# MaUWB_DSTO_Pro_with_Display_v1_0.net
KiCad netlist of a schematic drawn in EAGLE
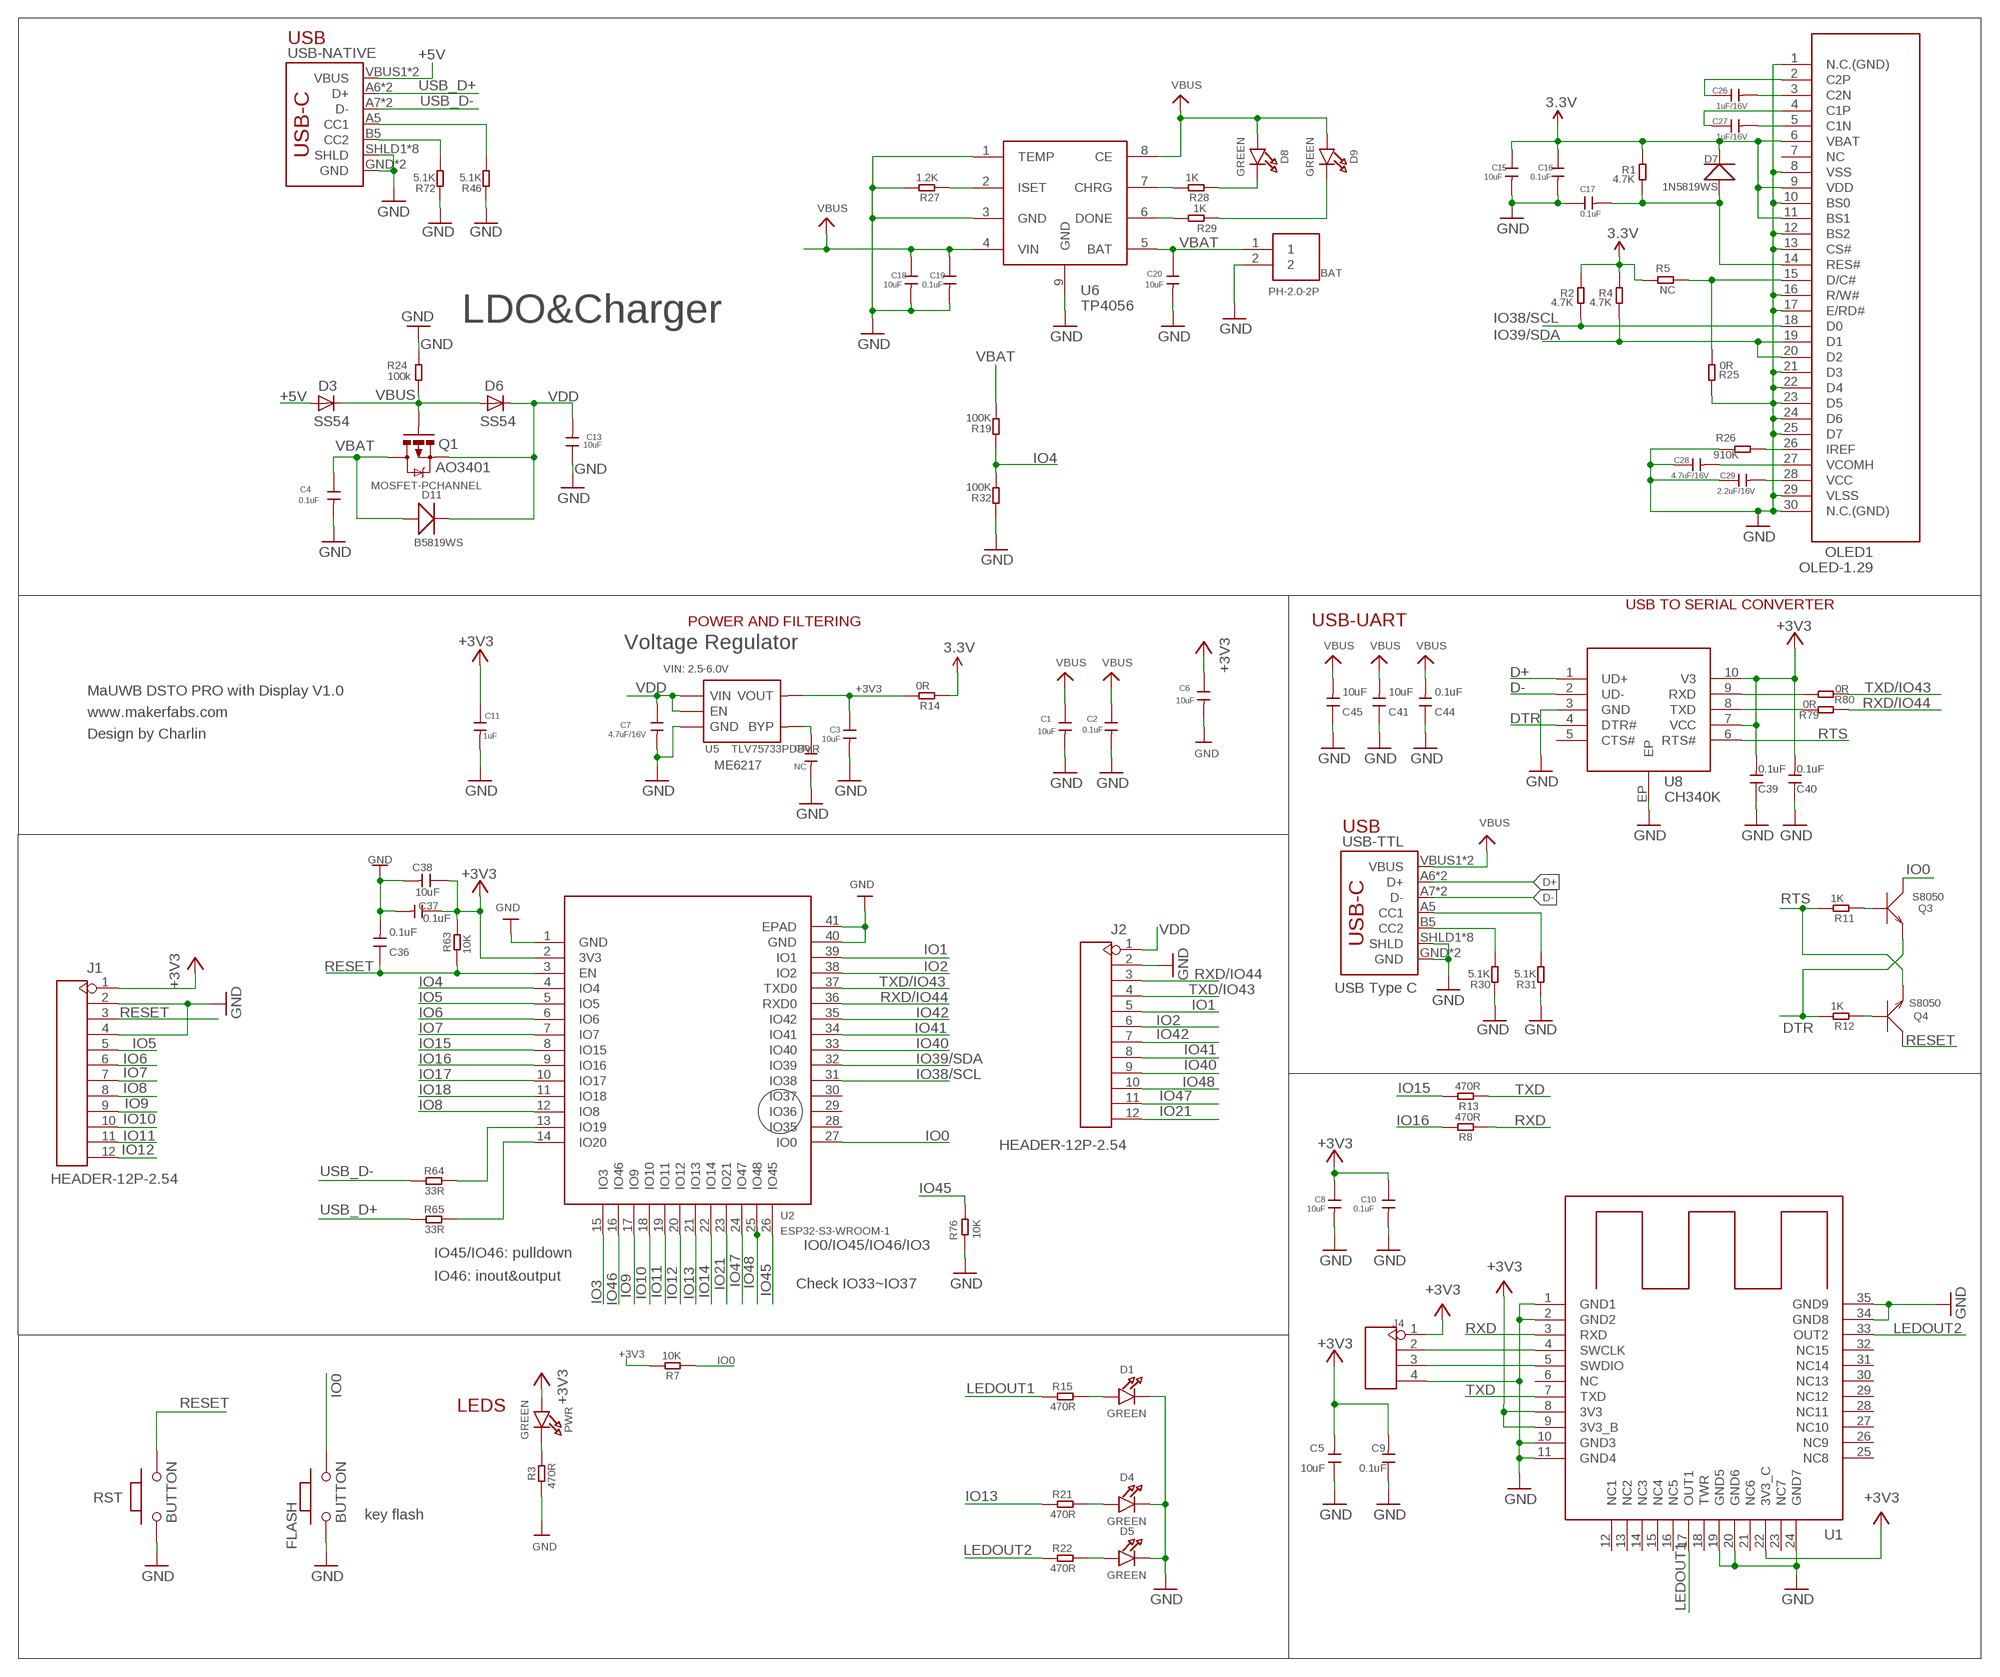
[diagram p0: schematic, sheet 1]

(export (version "E")
  (design (tool "Eeschema 10.0.6"))
  (components
    (comp (ref "BAT")
      (value "PH-2.0-2P")
      (footprint "eagle-import:PH-2.0-2P")
      (libsource (lib "eagle-import") (part "PH-2.0-2P"))
    )
    (comp (ref "C1")
      (value "10uF")
      (footprint "eagle-import:0603")
      (libsource (lib "eagle-import") (part "C-0603"))
    )
    (comp (ref "C2")
      (value "0.1uF")
      (footprint "eagle-import:0603")
      (libsource (lib "eagle-import") (part "C-0603"))
    )
    (comp (ref "C3")
      (value "10uF")
      (footprint "eagle-import:0603")
      (libsource (lib "eagle-import") (part "C-0603"))
    )
    (comp (ref "C4")
      (value "0.1uF")
      (footprint "eagle-import:0603")
      (libsource (lib "eagle-import") (part "C-0603"))
    )
    (comp (ref "C5")
      (value "10uF")
      (footprint "eagle-import:DISCRETE_C0402")
      (libsource (lib "eagle-import") (part "DISCRETE_C-0402"))
    )
    (comp (ref "C6")
      (value "10uF")
      (footprint "eagle-import:0603")
      (libsource (lib "eagle-import") (part "C-0603"))
    )
    (comp (ref "C7")
      (value "4.7uF/16V")
      (footprint "eagle-import:0603")
      (libsource (lib "eagle-import") (part "C-0603"))
    )
    (comp (ref "C8")
      (value "10uF")
      (footprint "eagle-import:0603")
      (libsource (lib "eagle-import") (part "C-0603"))
    )
    (comp (ref "C9")
      (value "0.1uF")
      (footprint "eagle-import:DISCRETE_C0402")
      (libsource (lib "eagle-import") (part "DISCRETE_C-0402"))
    )
    (comp (ref "C10")
      (value "0.1uF")
      (footprint "eagle-import:0603")
      (libsource (lib "eagle-import") (part "C-0603"))
    )
    (comp (ref "C11")
      (value "1uF")
      (footprint "eagle-import:0603")
      (libsource (lib "eagle-import") (part "C-0603"))
    )
    (comp (ref "C13")
      (value "10uF")
      (footprint "eagle-import:0603")
      (libsource (lib "eagle-import") (part "C-0603"))
    )
    (comp (ref "C15")
      (value "10uF")
      (footprint "eagle-import:0603")
      (libsource (lib "eagle-import") (part "C-0603"))
    )
    (comp (ref "C16")
      (value "0.1uF")
      (footprint "eagle-import:0603")
      (libsource (lib "eagle-import") (part "C-0603"))
    )
    (comp (ref "C17")
      (value "0.1uF")
      (footprint "eagle-import:0603")
      (libsource (lib "eagle-import") (part "C-0603"))
    )
    (comp (ref "C18")
      (value "10uF")
      (footprint "eagle-import:0603")
      (libsource (lib "eagle-import") (part "C-0603"))
    )
    (comp (ref "C19")
      (value "0.1uF")
      (footprint "eagle-import:0603")
      (libsource (lib "eagle-import") (part "C-0603"))
    )
    (comp (ref "C20")
      (value "10uF")
      (footprint "eagle-import:0603")
      (libsource (lib "eagle-import") (part "C-0603"))
    )
    (comp (ref "C26")
      (value "1uF/16V")
      (footprint "eagle-import:0603")
      (libsource (lib "eagle-import") (part "C-0603"))
    )
    (comp (ref "C27")
      (value "1uF/16V")
      (footprint "eagle-import:0603")
      (libsource (lib "eagle-import") (part "C-0603"))
    )
    (comp (ref "C28")
      (value "4.7uF/16V")
      (footprint "eagle-import:0603")
      (libsource (lib "eagle-import") (part "C-0603"))
    )
    (comp (ref "C29")
      (value "2.2uF/16V")
      (footprint "eagle-import:0603")
      (libsource (lib "eagle-import") (part "C-0603"))
    )
    (comp (ref "C30")
      (value "NC")
      (footprint "eagle-import:0603")
      (libsource (lib "eagle-import") (part "C-0603"))
    )
    (comp (ref "C36")
      (value "0.1uF")
      (footprint "eagle-import:DISCRETE_C0603")
      (libsource (lib "eagle-import") (part "DISCRETE_C-0603"))
    )
    (comp (ref "C37")
      (value "0.1uF")
      (footprint "eagle-import:DISCRETE_C0603")
      (libsource (lib "eagle-import") (part "DISCRETE_C-0603"))
    )
    (comp (ref "C38")
      (value "10uF")
      (footprint "eagle-import:DISCRETE_C0603")
      (libsource (lib "eagle-import") (part "DISCRETE_C-0603"))
    )
    (comp (ref "C39")
      (value "0.1uF")
      (footprint "eagle-import:DISCRETE_C0603")
      (libsource (lib "eagle-import") (part "DISCRETE_C-0603"))
    )
    (comp (ref "C40")
      (value "0.1uF")
      (footprint "eagle-import:DISCRETE_C0603")
      (libsource (lib "eagle-import") (part "DISCRETE_C-0603"))
    )
    (comp (ref "C41")
      (value "10uF")
      (footprint "eagle-import:DISCRETE_C0603")
      (libsource (lib "eagle-import") (part "DISCRETE_C-0603"))
    )
    (comp (ref "C44")
      (value "0.1uF")
      (footprint "eagle-import:DISCRETE_C0603")
      (libsource (lib "eagle-import") (part "DISCRETE_C-0603"))
    )
    (comp (ref "C45")
      (value "10uF")
      (footprint "eagle-import:DISCRETE_C0603")
      (libsource (lib "eagle-import") (part "DISCRETE_C-0603"))
    )
    (comp (ref "D1")
      (value "GREEN")
      (footprint "eagle-import:CHIPLED_0805_NOOUTLINE")
      (libsource (lib "eagle-import") (part "LED0805_NOOUTLINE"))
    )
    (comp (ref "D3")
      (value "SS54")
      (footprint "eagle-import:DO-214AC")
      (libsource (lib "eagle-import") (part "DIODE-DO-214AC"))
    )
    (comp (ref "D4")
      (value "GREEN")
      (footprint "eagle-import:CHIPLED_0805_NOOUTLINE")
      (libsource (lib "eagle-import") (part "LED0805_NOOUTLINE"))
    )
    (comp (ref "D5")
      (value "GREEN")
      (footprint "eagle-import:CHIPLED_0805_NOOUTLINE")
      (libsource (lib "eagle-import") (part "LED0805_NOOUTLINE"))
    )
    (comp (ref "D6")
      (value "SS54")
      (footprint "eagle-import:DO-214AC")
      (libsource (lib "eagle-import") (part "DIODE-DO-214AC"))
    )
    (comp (ref "D7")
      (value "1N5819WS")
      (footprint "eagle-import:SOD323")
      (libsource (lib "eagle-import") (part "D'0805'"))
    )
    (comp (ref "D8")
      (value "GREEN")
      (footprint "eagle-import:CHIPLED_0805_NOOUTLINE")
      (libsource (lib "eagle-import") (part "LED0805_NOOUTLINE"))
    )
    (comp (ref "D9")
      (value "GREEN")
      (footprint "eagle-import:CHIPLED_0805_NOOUTLINE")
      (libsource (lib "eagle-import") (part "LED0805_NOOUTLINE"))
    )
    (comp (ref "D11")
      (value "B5819WS")
      (footprint "eagle-import:SOD323")
      (libsource (lib "eagle-import") (part "D'0805'"))
    )
    (comp (ref "FLASH")
      (value "BUTTON")
      (footprint "eagle-import:157SW")
      (libsource (lib "eagle-import") (part "PB157"))
    )
    (comp (ref "J1")
      (value "HEADER-12P-2.54")
      (footprint "eagle-import:12P-2.54")
      (libsource (lib "eagle-import") (part "HEADER-12P-2.54"))
    )
    (comp (ref "J2")
      (value "HEADER-12P-2.54")
      (footprint "eagle-import:12P-2.54")
      (libsource (lib "eagle-import") (part "HEADER-12P-2.54"))
    )
    (comp (ref "J4")
      (value "HEADER-4P-60/35MILROUND")
      (footprint "eagle-import:4P-65_35ROUND")
      (libsource (lib "eagle-import") (part "HEADER-4P-60/35MILROUND"))
    )
    (comp (ref "OLED1")
      (value "OLED-1.29")
      (footprint "eagle-import:OLED-1.29")
      (libsource (lib "eagle-import") (part "OLED-1.29"))
    )
    (comp (ref "PWR")
      (value "GREEN")
      (footprint "eagle-import:CHIPLED_0805_NOOUTLINE")
      (libsource (lib "eagle-import") (part "LED0805_NOOUTLINE"))
    )
    (comp (ref "Q1")
      (value "MOSFET-PCHANNEL")
      (footprint "eagle-import:SOT23-3")
      (libsource (lib "eagle-import") (part "MOSFET-PCHANNEL"))
    )
    (comp (ref "Q3")
      (value "S8050")
      (footprint "eagle-import:SOT23")
      (libsource (lib "eagle-import") (part "TRANSISTOR-NPN-SOT23"))
    )
    (comp (ref "Q4")
      (value "S8050")
      (footprint "eagle-import:SOT23")
      (libsource (lib "eagle-import") (part "TRANSISTOR-NPN-SOT23"))
    )
    (comp (ref "R1")
      (value "4.7K")
      (footprint "eagle-import:R0603")
      (libsource (lib "eagle-import") (part "R-0603"))
    )
    (comp (ref "R2")
      (value "4.7K")
      (footprint "eagle-import:R0603")
      (libsource (lib "eagle-import") (part "R-0603"))
    )
    (comp (ref "R3")
      (value "470R")
      (footprint "eagle-import:R0603")
      (libsource (lib "eagle-import") (part "R-0603"))
    )
    (comp (ref "R4")
      (value "4.7K")
      (footprint "eagle-import:R0603")
      (libsource (lib "eagle-import") (part "R-0603"))
    )
    (comp (ref "R5")
      (value "NC")
      (footprint "eagle-import:R0603")
      (libsource (lib "eagle-import") (part "R-0603"))
    )
    (comp (ref "R7")
      (value "10K")
      (footprint "eagle-import:R0603")
      (libsource (lib "eagle-import") (part "R-0603"))
    )
    (comp (ref "R8")
      (value "470R")
      (footprint "eagle-import:R0603")
      (libsource (lib "eagle-import") (part "R-0603"))
    )
    (comp (ref "R11")
      (value "1K")
      (footprint "eagle-import:R0603")
      (libsource (lib "eagle-import") (part "R-0603"))
    )
    (comp (ref "R12")
      (value "1K")
      (footprint "eagle-import:R0603")
      (libsource (lib "eagle-import") (part "R-0603"))
    )
    (comp (ref "R13")
      (value "470R")
      (footprint "eagle-import:R0603")
      (libsource (lib "eagle-import") (part "R-0603"))
    )
    (comp (ref "R14")
      (value "0R")
      (footprint "eagle-import:R0603")
      (libsource (lib "eagle-import") (part "R-0603"))
    )
    (comp (ref "R15")
      (value "470R")
      (footprint "eagle-import:R0603")
      (libsource (lib "eagle-import") (part "R-0603"))
    )
    (comp (ref "R19")
      (value "100K")
      (footprint "eagle-import:DISCRETE_R0603")
      (libsource (lib "eagle-import") (part "DISCRETE_R-0603"))
    )
    (comp (ref "R21")
      (value "470R")
      (footprint "eagle-import:R0603")
      (libsource (lib "eagle-import") (part "R-0603"))
    )
    (comp (ref "R22")
      (value "470R")
      (footprint "eagle-import:R0603")
      (libsource (lib "eagle-import") (part "R-0603"))
    )
    (comp (ref "R24")
      (value "100k")
      (footprint "eagle-import:R0603")
      (libsource (lib "eagle-import") (part "R-0603"))
    )
    (comp (ref "R25")
      (value "0R")
      (footprint "eagle-import:R0603")
      (libsource (lib "eagle-import") (part "R-0603"))
    )
    (comp (ref "R26")
      (value "910K")
      (footprint "eagle-import:R0603")
      (libsource (lib "eagle-import") (part "R-0603"))
    )
    (comp (ref "R27")
      (value "1.2K")
      (footprint "eagle-import:R0603")
      (libsource (lib "eagle-import") (part "R-0603"))
    )
    (comp (ref "R28")
      (value "1K")
      (footprint "eagle-import:R0603")
      (libsource (lib "eagle-import") (part "R-0603"))
    )
    (comp (ref "R29")
      (value "1K")
      (footprint "eagle-import:R0603")
      (libsource (lib "eagle-import") (part "R-0603"))
    )
    (comp (ref "R30")
      (value "5.1K")
      (footprint "eagle-import:DISCRETE_R0603")
      (libsource (lib "eagle-import") (part "DISCRETE_R-0603"))
    )
    (comp (ref "R31")
      (value "5.1K")
      (footprint "eagle-import:DISCRETE_R0603")
      (libsource (lib "eagle-import") (part "DISCRETE_R-0603"))
    )
    (comp (ref "R32")
      (value "100K")
      (footprint "eagle-import:DISCRETE_R0603")
      (libsource (lib "eagle-import") (part "DISCRETE_R-0603"))
    )
    (comp (ref "R46")
      (value "5.1K")
      (footprint "eagle-import:DISCRETE_R0603")
      (libsource (lib "eagle-import") (part "DISCRETE_R-0603"))
    )
    (comp (ref "R63")
      (value "10K")
      (footprint "eagle-import:R0603")
      (libsource (lib "eagle-import") (part "R-0603"))
    )
    (comp (ref "R64")
      (value "33R")
      (footprint "eagle-import:R0603")
      (libsource (lib "eagle-import") (part "R-0603"))
    )
    (comp (ref "R65")
      (value "33R")
      (footprint "eagle-import:R0603")
      (libsource (lib "eagle-import") (part "R-0603"))
    )
    (comp (ref "R72")
      (value "5.1K")
      (footprint "eagle-import:DISCRETE_R0603")
      (libsource (lib "eagle-import") (part "DISCRETE_R-0603"))
    )
    (comp (ref "R76")
      (value "10K")
      (footprint "eagle-import:R0603")
      (libsource (lib "eagle-import") (part "R-0603"))
    )
    (comp (ref "R79")
      (value "0R")
      (footprint "eagle-import:R0603")
      (libsource (lib "eagle-import") (part "R-0603"))
    )
    (comp (ref "R80")
      (value "0R")
      (footprint "eagle-import:R0603")
      (libsource (lib "eagle-import") (part "R-0603"))
    )
    (comp (ref "RST")
      (value "BUTTON")
      (footprint "eagle-import:157SW")
      (libsource (lib "eagle-import") (part "PB157"))
    )
    (comp (ref "U1")
      (value "UWB-DSTO")
      (footprint "eagle-import:UWB-DSTO")
      (libsource (lib "eagle-import") (part "UWB-DSTO"))
    )
    (comp (ref "U2")
      (value "ESP32-S3-WROOM-1")
      (footprint "eagle-import:ESP32-S3-WROOM-1")
      (libsource (lib "eagle-import") (part "ESP32-S3-WROOM-1"))
    )
    (comp (ref "U5")
      (value "TLV75733PDBVR")
      (footprint "eagle-import:SOT23-5")
      (libsource (lib "eagle-import") (part "SPX3819"))
    )
    (comp (ref "U6")
      (value "TP4056")
      (footprint "eagle-import:SOP8-1.27P")
      (libsource (lib "eagle-import") (part "TP4056"))
    )
    (comp (ref "U8")
      (value "CH340K")
      (footprint "eagle-import:ESOP-10-EP-150MIL")
      (libsource (lib "eagle-import") (part "CH340K"))
    )
    (comp (ref "USB-NATIVE")
      (value "USB_C5")
      (footprint "eagle-import:USB-C-16P-5")
      (libsource (lib "eagle-import") (part "USB_C5"))
    )
    (comp (ref "USB-TTL")
      (value "USB_C5")
      (footprint "eagle-import:USB-C-16P-5")
      (libsource (lib "eagle-import") (part "USB_C5"))
    )
  )
  (nets
    (net (code "1") (name "+3V3") (class "Default")
      (node (ref "C10") (pin "1") (pinfunction "1_1") (pintype "passive"))
      (node (ref "C11") (pin "1") (pinfunction "1_1") (pintype "passive"))
      (node (ref "C3") (pin "1") (pinfunction "1_1") (pintype "passive"))
      (node (ref "C37") (pin "1") (pinfunction "1_1") (pintype "passive"))
      (node (ref "C38") (pin "1") (pinfunction "1_1") (pintype "passive"))
      (node (ref "C39") (pin "2") (pinfunction "2_2") (pintype "passive"))
      (node (ref "C40") (pin "2") (pinfunction "2_2") (pintype "passive"))
      (node (ref "C5") (pin "2") (pinfunction "2_2") (pintype "passive"))
      (node (ref "C6") (pin "1") (pinfunction "1_1") (pintype "passive"))
      (node (ref "C8") (pin "1") (pinfunction "1_1") (pintype "passive"))
      (node (ref "C9") (pin "2") (pinfunction "2_2") (pintype "passive"))
      (node (ref "J1") (pin "1") (pinfunction "1_1") (pintype "bidirectional"))
      (node (ref "J4") (pin "1") (pinfunction "P$1_1") (pintype "bidirectional"))
      (node (ref "PWR") (pin "A") (pinfunction "A_A") (pintype "passive"))
      (node (ref "R14") (pin "2") (pinfunction "2_2") (pintype "passive"))
      (node (ref "R63") (pin "2") (pinfunction "2_2") (pintype "passive"))
      (node (ref "R7") (pin "2") (pinfunction "2_2") (pintype "passive"))
      (node (ref "U1") (pin "22") (pinfunction "3V3_C_22") (pintype "bidirectional"))
      (node (ref "U1") (pin "8") (pinfunction "3V3_8") (pintype "bidirectional"))
      (node (ref "U1") (pin "9") (pinfunction "3V3_B_9") (pintype "bidirectional"))
      (node (ref "U2") (pin "2") (pinfunction "3V3_2") (pintype "bidirectional"))
      (node (ref "U5") (pin "5") (pinfunction "VOUT_5") (pintype "bidirectional"))
      (node (ref "U8") (pin "10") (pinfunction "V3_10") (pintype "bidirectional"))
      (node (ref "U8") (pin "7") (pinfunction "VCC_7") (pintype "bidirectional"))
    )
    (net (code "2") (name "/+5V") (class "Default")
      (node (ref "D3") (pin "A") (pinfunction "A_A") (pintype "passive"))
      (node (ref "USB-NATIVE") (pin "VBUS1") (pinfunction "VBUS_VBUS1") (pintype "bidirectional"))
      (node (ref "USB-NATIVE") (pin "VBUS2") (pinfunction "VBUS_VBUS2") (pintype "bidirectional"))
    )
    (net (code "3") (name "/DTR") (class "Default")
      (node (ref "Q3") (pin "2") (pinfunction "E_2") (pintype "passive"))
      (node (ref "R12") (pin "2") (pinfunction "2_2") (pintype "passive"))
      (node (ref "U8") (pin "4") (pinfunction "DTR#_4") (pintype "bidirectional"))
    )
    (net (code "4") (name "/IO0") (class "Default")
      (node (ref "FLASH") (pin "2") (pinfunction "2_2") (pintype "passive"))
      (node (ref "Q3") (pin "3") (pinfunction "C_3") (pintype "passive"))
      (node (ref "R7") (pin "1") (pinfunction "1_1") (pintype "passive"))
      (node (ref "U2") (pin "27") (pinfunction "IO0_27") (pintype "bidirectional"))
    )
    (net (code "5") (name "/IO1") (class "Default")
      (node (ref "J2") (pin "5") (pinfunction "5_5") (pintype "bidirectional"))
      (node (ref "U2") (pin "39") (pinfunction "IO1_39") (pintype "bidirectional"))
    )
    (net (code "6") (name "/IO2") (class "Default")
      (node (ref "J2") (pin "6") (pinfunction "6_6") (pintype "bidirectional"))
      (node (ref "U2") (pin "38") (pinfunction "IO2_38") (pintype "bidirectional"))
    )
    (net (code "7") (name "/IO3") (class "Default")
      (node (ref "U2") (pin "15") (pinfunction "IO3_15") (pintype "bidirectional"))
    )
    (net (code "8") (name "/IO4") (class "Default")
      (node (ref "R19") (pin "1") (pinfunction "1_1") (pintype "passive"))
      (node (ref "R32") (pin "2") (pinfunction "2_2") (pintype "passive"))
      (node (ref "U2") (pin "4") (pinfunction "IO4_4") (pintype "bidirectional"))
    )
    (net (code "9") (name "/IO5") (class "Default")
      (node (ref "J1") (pin "5") (pinfunction "5_5") (pintype "bidirectional"))
      (node (ref "U2") (pin "5") (pinfunction "IO5_5") (pintype "bidirectional"))
    )
    (net (code "10") (name "/IO6") (class "Default")
      (node (ref "J1") (pin "6") (pinfunction "6_6") (pintype "bidirectional"))
      (node (ref "U2") (pin "6") (pinfunction "IO6_6") (pintype "bidirectional"))
    )
    (net (code "11") (name "/IO7") (class "Default")
      (node (ref "J1") (pin "7") (pinfunction "7_7") (pintype "bidirectional"))
      (node (ref "U2") (pin "7") (pinfunction "IO7_7") (pintype "bidirectional"))
    )
    (net (code "12") (name "/IO8") (class "Default")
      (node (ref "J1") (pin "8") (pinfunction "8_8") (pintype "bidirectional"))
      (node (ref "U2") (pin "12") (pinfunction "IO8_12") (pintype "bidirectional"))
    )
    (net (code "13") (name "/IO9") (class "Default")
      (node (ref "J1") (pin "9") (pinfunction "9_9") (pintype "bidirectional"))
      (node (ref "U2") (pin "17") (pinfunction "IO9_17") (pintype "bidirectional"))
    )
    (net (code "14") (name "/IO10") (class "Default")
      (node (ref "J1") (pin "10") (pinfunction "10_10") (pintype "bidirectional"))
      (node (ref "U2") (pin "18") (pinfunction "IO10_18") (pintype "bidirectional"))
    )
    (net (code "15") (name "/IO11") (class "Default")
      (node (ref "J1") (pin "11") (pinfunction "11_11") (pintype "bidirectional"))
      (node (ref "U2") (pin "19") (pinfunction "IO11_19") (pintype "bidirectional"))
    )
    (net (code "16") (name "/IO12") (class "Default")
      (node (ref "J1") (pin "12") (pinfunction "12_12") (pintype "bidirectional"))
      (node (ref "U2") (pin "20") (pinfunction "IO12_20") (pintype "bidirectional"))
    )
    (net (code "17") (name "/IO13") (class "Default")
      (node (ref "R21") (pin "1") (pinfunction "1_1") (pintype "passive"))
      (node (ref "U2") (pin "21") (pinfunction "IO13_21") (pintype "bidirectional"))
    )
    (net (code "18") (name "/IO14") (class "Default")
      (node (ref "U2") (pin "22") (pinfunction "IO14_22") (pintype "bidirectional"))
    )
    (net (code "19") (name "/IO15") (class "Default")
      (node (ref "R13") (pin "2") (pinfunction "2_2") (pintype "passive"))
      (node (ref "U2") (pin "8") (pinfunction "IO15_8") (pintype "bidirectional"))
    )
    (net (code "20") (name "/IO16") (class "Default")
      (node (ref "R8") (pin "2") (pinfunction "2_2") (pintype "passive"))
      (node (ref "U2") (pin "9") (pinfunction "IO16_9") (pintype "bidirectional"))
    )
    (net (code "21") (name "/IO17") (class "Default")
      (node (ref "U2") (pin "10") (pinfunction "IO17_10") (pintype "bidirectional"))
    )
    (net (code "22") (name "/IO18") (class "Default")
      (node (ref "U2") (pin "11") (pinfunction "IO18_11") (pintype "bidirectional"))
    )
    (net (code "23") (name "/IO21") (class "Default")
      (node (ref "J2") (pin "12") (pinfunction "12_12") (pintype "bidirectional"))
      (node (ref "U2") (pin "23") (pinfunction "IO21_23") (pintype "bidirectional"))
    )
    (net (code "24") (name "/IO38{slash}SCL") (class "Default")
      (node (ref "OLED1") (pin "18") (pinfunction "D0_18") (pintype "bidirectional"))
      (node (ref "R2") (pin "1") (pinfunction "1_1") (pintype "passive"))
      (node (ref "U2") (pin "31") (pinfunction "IO38_31") (pintype "bidirectional"))
    )
    (net (code "25") (name "/IO39{slash}SDA") (class "Default")
      (node (ref "OLED1") (pin "19") (pinfunction "D1_19") (pintype "bidirectional"))
      (node (ref "OLED1") (pin "20") (pinfunction "D2_20") (pintype "bidirectional"))
      (node (ref "R4") (pin "1") (pinfunction "1_1") (pintype "passive"))
      (node (ref "U2") (pin "32") (pinfunction "IO39_32") (pintype "bidirectional"))
    )
    (net (code "26") (name "/IO40") (class "Default")
      (node (ref "J2") (pin "9") (pinfunction "9_9") (pintype "bidirectional"))
      (node (ref "U2") (pin "33") (pinfunction "IO40_33") (pintype "bidirectional"))
    )
    (net (code "27") (name "/IO41") (class "Default")
      (node (ref "J2") (pin "8") (pinfunction "8_8") (pintype "bidirectional"))
      (node (ref "U2") (pin "34") (pinfunction "IO41_34") (pintype "bidirectional"))
    )
    (net (code "28") (name "/IO42") (class "Default")
      (node (ref "J2") (pin "7") (pinfunction "7_7") (pintype "bidirectional"))
      (node (ref "U2") (pin "35") (pinfunction "IO42_35") (pintype "bidirectional"))
    )
    (net (code "29") (name "/IO45") (class "Default")
      (node (ref "R76") (pin "2") (pinfunction "2_2") (pintype "passive"))
      (node (ref "U2") (pin "26") (pinfunction "IO45_26") (pintype "bidirectional"))
    )
    (net (code "30") (name "/IO46") (class "Default")
      (node (ref "U2") (pin "16") (pinfunction "IO46_16") (pintype "bidirectional"))
    )
    (net (code "31") (name "/IO47") (class "Default")
      (node (ref "J2") (pin "11") (pinfunction "11_11") (pintype "bidirectional"))
      (node (ref "U2") (pin "24") (pinfunction "IO47_24") (pintype "bidirectional"))
    )
    (net (code "32") (name "/IO48") (class "Default")
      (node (ref "J2") (pin "10") (pinfunction "10_10") (pintype "bidirectional"))
      (node (ref "U2") (pin "25") (pinfunction "IO48_25") (pintype "bidirectional"))
    )
    (net (code "33") (name "/LEDOUT1") (class "Default")
      (node (ref "R15") (pin "1") (pinfunction "1_1") (pintype "passive"))
      (node (ref "U1") (pin "17") (pinfunction "OUT1_17") (pintype "bidirectional"))
    )
    (net (code "34") (name "/LEDOUT2") (class "Default")
      (node (ref "R22") (pin "1") (pinfunction "1_1") (pintype "passive"))
      (node (ref "U1") (pin "33") (pinfunction "OUT2_33") (pintype "bidirectional"))
    )
    (net (code "35") (name "/RESET") (class "Default")
      (node (ref "C36") (pin "1") (pinfunction "1_1") (pintype "passive"))
      (node (ref "J1") (pin "3") (pinfunction "3_3") (pintype "bidirectional"))
      (node (ref "Q4") (pin "3") (pinfunction "C_3") (pintype "passive"))
      (node (ref "R63") (pin "1") (pinfunction "1_1") (pintype "passive"))
      (node (ref "RST") (pin "2") (pinfunction "2_2") (pintype "passive"))
      (node (ref "U2") (pin "3") (pinfunction "EN_3") (pintype "bidirectional"))
    )
    (net (code "36") (name "/RTS") (class "Default")
      (node (ref "Q4") (pin "2") (pinfunction "E_2") (pintype "passive"))
      (node (ref "R11") (pin "2") (pinfunction "2_2") (pintype "passive"))
      (node (ref "U8") (pin "6") (pinfunction "RTS#_6") (pintype "bidirectional"))
    )
    (net (code "37") (name "/RXD") (class "Default")
      (node (ref "R8") (pin "1") (pinfunction "1_1") (pintype "passive"))
      (node (ref "U1") (pin "3") (pinfunction "RXD_3") (pintype "bidirectional"))
    )
    (net (code "38") (name "/RXD{slash}IO44") (class "Default")
      (node (ref "J2") (pin "3") (pinfunction "3_3") (pintype "bidirectional"))
      (node (ref "R79") (pin "1") (pinfunction "1_1") (pintype "passive"))
      (node (ref "U2") (pin "36") (pinfunction "RXD0_36") (pintype "bidirectional"))
    )
    (net (code "39") (name "/TXD") (class "Default")
      (node (ref "R13") (pin "1") (pinfunction "1_1") (pintype "passive"))
      (node (ref "U1") (pin "7") (pinfunction "TXD_7") (pintype "bidirectional"))
    )
    (net (code "40") (name "/TXD{slash}IO43") (class "Default")
      (node (ref "J2") (pin "4") (pinfunction "4_4") (pintype "bidirectional"))
      (node (ref "R80") (pin "1") (pinfunction "1_1") (pintype "passive"))
      (node (ref "U2") (pin "37") (pinfunction "TXD0_37") (pintype "bidirectional"))
    )
    (net (code "41") (name "/USB_D+") (class "Default")
      (node (ref "R65") (pin "1") (pinfunction "1_1") (pintype "passive"))
      (node (ref "USB-NATIVE") (pin "A6") (pinfunction "D+_A6") (pintype "bidirectional"))
      (node (ref "USB-NATIVE") (pin "B6") (pinfunction "D+_B6") (pintype "bidirectional"))
    )
    (net (code "42") (name "/USB_D-") (class "Default")
      (node (ref "R64") (pin "1") (pinfunction "1_1") (pintype "passive"))
      (node (ref "USB-NATIVE") (pin "A7") (pinfunction "D-_A7") (pintype "bidirectional"))
      (node (ref "USB-NATIVE") (pin "B7") (pinfunction "D-_B7") (pintype "bidirectional"))
    )
    (net (code "43") (name "/VBAT") (class "Default")
      (node (ref "BAT") (pin "1") (pinfunction "1_1") (pintype "bidirectional"))
      (node (ref "C20") (pin "1") (pinfunction "1_1") (pintype "passive"))
      (node (ref "C4") (pin "1") (pinfunction "1_1") (pintype "passive"))
      (node (ref "D11") (pin "+") (pinfunction "+_+") (pintype "passive"))
      (node (ref "Q1") (pin "3") (pinfunction "D_3") (pintype "passive"))
      (node (ref "R19") (pin "2") (pinfunction "2_2") (pintype "passive"))
      (node (ref "U6") (pin "5") (pinfunction "BAT_5") (pintype "bidirectional"))
    )
    (net (code "44") (name "/VDD") (class "Default")
      (node (ref "C13") (pin "2") (pinfunction "2_2") (pintype "passive"))
      (node (ref "C7") (pin "1") (pinfunction "1_1") (pintype "passive"))
      (node (ref "D11") (pin "-") (pinfunction "-_-") (pintype "passive"))
      (node (ref "D6") (pin "C") (pinfunction "C_C") (pintype "passive"))
      (node (ref "J2") (pin "1") (pinfunction "1_1") (pintype "bidirectional"))
      (node (ref "Q1") (pin "2") (pinfunction "S_2") (pintype "passive"))
      (node (ref "U5") (pin "1") (pinfunction "VIN_1") (pintype "bidirectional"))
      (node (ref "U5") (pin "3") (pinfunction "EN_3") (pintype "bidirectional"))
    )
    (net (code "45") (name "3.3V") (class "Default")
      (node (ref "C15") (pin "1") (pinfunction "1_1") (pintype "passive"))
      (node (ref "C16") (pin "1") (pinfunction "1_1") (pintype "passive"))
      (node (ref "D7") (pin "-") (pinfunction "-_-") (pintype "passive"))
      (node (ref "OLED1") (pin "11") (pinfunction "BS1_11") (pintype "bidirectional"))
      (node (ref "OLED1") (pin "6") (pinfunction "VBAT_6") (pintype "bidirectional"))
      (node (ref "OLED1") (pin "9") (pinfunction "VDD_9") (pintype "bidirectional"))
      (node (ref "R1") (pin "2") (pinfunction "2_2") (pintype "passive"))
      (node (ref "R14") (pin "1") (pinfunction "1_1") (pintype "passive"))
      (node (ref "R2") (pin "2") (pinfunction "2_2") (pintype "passive"))
      (node (ref "R4") (pin "2") (pinfunction "2_2") (pintype "passive"))
      (node (ref "R5") (pin "2") (pinfunction "2_2") (pintype "passive"))
    )
    (net (code "46") (name "D+") (class "Default")
      (node (ref "U8") (pin "1") (pinfunction "UD+_1") (pintype "bidirectional"))
      (node (ref "USB-TTL") (pin "A6") (pinfunction "D+_A6") (pintype "bidirectional"))
      (node (ref "USB-TTL") (pin "B6") (pinfunction "D+_B6") (pintype "bidirectional"))
    )
    (net (code "47") (name "D-") (class "Default")
      (node (ref "U8") (pin "2") (pinfunction "UD-_2") (pintype "bidirectional"))
      (node (ref "USB-TTL") (pin "A7") (pinfunction "D-_A7") (pintype "bidirectional"))
      (node (ref "USB-TTL") (pin "B7") (pinfunction "D-_B7") (pintype "bidirectional"))
    )
    (net (code "48") (name "GND") (class "Default")
      (node (ref "BAT") (pin "2") (pinfunction "2_2") (pintype "bidirectional"))
      (node (ref "C1") (pin "2") (pinfunction "2_2") (pintype "passive"))
      (node (ref "C10") (pin "2") (pinfunction "2_2") (pintype "passive"))
      (node (ref "C11") (pin "2") (pinfunction "2_2") (pintype "passive"))
      (node (ref "C13") (pin "1") (pinfunction "1_1") (pintype "passive"))
      (node (ref "C15") (pin "2") (pinfunction "2_2") (pintype "passive"))
      (node (ref "C16") (pin "2") (pinfunction "2_2") (pintype "passive"))
      (node (ref "C17") (pin "1") (pinfunction "1_1") (pintype "passive"))
      (node (ref "C18") (pin "2") (pinfunction "2_2") (pintype "passive"))
      (node (ref "C19") (pin "2") (pinfunction "2_2") (pintype "passive"))
      (node (ref "C2") (pin "2") (pinfunction "2_2") (pintype "passive"))
      (node (ref "C20") (pin "2") (pinfunction "2_2") (pintype "passive"))
      (node (ref "C28") (pin "1") (pinfunction "1_1") (pintype "passive"))
      (node (ref "C29") (pin "1") (pinfunction "1_1") (pintype "passive"))
      (node (ref "C3") (pin "2") (pinfunction "2_2") (pintype "passive"))
      (node (ref "C30") (pin "2") (pinfunction "2_2") (pintype "passive"))
      (node (ref "C36") (pin "2") (pinfunction "2_2") (pintype "passive"))
      (node (ref "C37") (pin "2") (pinfunction "2_2") (pintype "passive"))
      (node (ref "C38") (pin "2") (pinfunction "2_2") (pintype "passive"))
      (node (ref "C39") (pin "1") (pinfunction "1_1") (pintype "passive"))
      (node (ref "C4") (pin "2") (pinfunction "2_2") (pintype "passive"))
      (node (ref "C40") (pin "1") (pinfunction "1_1") (pintype "passive"))
      (node (ref "C41") (pin "1") (pinfunction "1_1") (pintype "passive"))
      (node (ref "C44") (pin "1") (pinfunction "1_1") (pintype "passive"))
      (node (ref "C45") (pin "1") (pinfunction "1_1") (pintype "passive"))
      (node (ref "C5") (pin "1") (pinfunction "1_1") (pintype "passive"))
      (node (ref "C6") (pin "2") (pinfunction "2_2") (pintype "passive"))
      (node (ref "C7") (pin "2") (pinfunction "2_2") (pintype "passive"))
      (node (ref "C8") (pin "2") (pinfunction "2_2") (pintype "passive"))
      (node (ref "C9") (pin "1") (pinfunction "1_1") (pintype "passive"))
      (node (ref "D1") (pin "C") (pinfunction "C_C") (pintype "passive"))
      (node (ref "D4") (pin "C") (pinfunction "C_C") (pintype "passive"))
      (node (ref "D5") (pin "C") (pinfunction "C_C") (pintype "passive"))
      (node (ref "FLASH") (pin "1") (pinfunction "1_1") (pintype "passive"))
      (node (ref "J1") (pin "2") (pinfunction "2_2") (pintype "bidirectional"))
      (node (ref "J1") (pin "4") (pinfunction "4_4") (pintype "bidirectional"))
      (node (ref "J2") (pin "2") (pinfunction "2_2") (pintype "bidirectional"))
      (node (ref "J4") (pin "4") (pinfunction "P$4_4") (pintype "bidirectional"))
      (node (ref "OLED1") (pin "1") (pinfunction "N.C.(GND)_1") (pintype "bidirectional"))
      (node (ref "OLED1") (pin "10") (pinfunction "BS0_10") (pintype "bidirectional"))
      (node (ref "OLED1") (pin "12") (pinfunction "BS2_12") (pintype "bidirectional"))
      (node (ref "OLED1") (pin "13") (pinfunction "CS#_13") (pintype "bidirectional"))
      (node (ref "OLED1") (pin "16") (pinfunction "R/W#_16") (pintype "bidirectional"))
      (node (ref "OLED1") (pin "17") (pinfunction "E/RD#_17") (pintype "bidirectional"))
      (node (ref "OLED1") (pin "21") (pinfunction "D3_21") (pintype "bidirectional"))
      (node (ref "OLED1") (pin "22") (pinfunction "D4_22") (pintype "bidirectional"))
      (node (ref "OLED1") (pin "23") (pinfunction "D5_23") (pintype "bidirectional"))
      (node (ref "OLED1") (pin "24") (pinfunction "D6_24") (pintype "bidirectional"))
      (node (ref "OLED1") (pin "25") (pinfunction "D7_25") (pintype "bidirectional"))
      (node (ref "OLED1") (pin "29") (pinfunction "VLSS_29") (pintype "bidirectional"))
      (node (ref "OLED1") (pin "30") (pinfunction "N.C.(GND)_30") (pintype "bidirectional"))
      (node (ref "OLED1") (pin "8") (pinfunction "VSS_8") (pintype "bidirectional"))
      (node (ref "R24") (pin "2") (pinfunction "2_2") (pintype "passive"))
      (node (ref "R25") (pin "2") (pinfunction "2_2") (pintype "passive"))
      (node (ref "R26") (pin "2") (pinfunction "2_2") (pintype "passive"))
      (node (ref "R27") (pin "2") (pinfunction "2_2") (pintype "passive"))
      (node (ref "R3") (pin "1") (pinfunction "1_1") (pintype "passive"))
      (node (ref "R30") (pin "1") (pinfunction "1_1") (pintype "passive"))
      (node (ref "R31") (pin "1") (pinfunction "1_1") (pintype "passive"))
      (node (ref "R32") (pin "1") (pinfunction "1_1") (pintype "passive"))
      (node (ref "R46") (pin "1") (pinfunction "1_1") (pintype "passive"))
      (node (ref "R72") (pin "1") (pinfunction "1_1") (pintype "passive"))
      (node (ref "R76") (pin "1") (pinfunction "1_1") (pintype "passive"))
      (node (ref "RST") (pin "1") (pinfunction "1_1") (pintype "passive"))
      (node (ref "U1") (pin "1") (pinfunction "GND1_1") (pintype "bidirectional"))
      (node (ref "U1") (pin "10") (pinfunction "GND3_10") (pintype "bidirectional"))
      (node (ref "U1") (pin "11") (pinfunction "GND4_11") (pintype "bidirectional"))
      (node (ref "U1") (pin "19") (pinfunction "GND5_19") (pintype "bidirectional"))
      (node (ref "U1") (pin "2") (pinfunction "GND2_2") (pintype "bidirectional"))
      (node (ref "U1") (pin "20") (pinfunction "GND6_20") (pintype "bidirectional"))
      (node (ref "U1") (pin "24") (pinfunction "GND7_24") (pintype "bidirectional"))
      (node (ref "U1") (pin "34") (pinfunction "GND8_34") (pintype "bidirectional"))
      (node (ref "U1") (pin "35") (pinfunction "GND9_35") (pintype "bidirectional"))
      (node (ref "U2") (pin "1") (pinfunction "GND_1") (pintype "bidirectional"))
      (node (ref "U2") (pin "40") (pinfunction "GND_40") (pintype "bidirectional"))
      (node (ref "U2") (pin "41") (pinfunction "EPAD_41") (pintype "bidirectional"))
      (node (ref "U5") (pin "2") (pinfunction "GND_2") (pintype "bidirectional"))
      (node (ref "U6") (pin "1") (pinfunction "TEMP_1") (pintype "bidirectional"))
      (node (ref "U6") (pin "3") (pinfunction "GND_3") (pintype "bidirectional"))
      (node (ref "U6") (pin "9") (pinfunction "GND_9") (pintype "bidirectional"))
      (node (ref "U8") (pin "3") (pinfunction "GND_3") (pintype "bidirectional"))
      (node (ref "U8") (pin "EP") (pinfunction "EP_EP") (pintype "bidirectional"))
      (node (ref "USB-NATIVE") (pin "GND") (pinfunction "GND_GND") (pintype "bidirectional"))
      (node (ref "USB-NATIVE") (pin "GND2") (pinfunction "GND_GND2") (pintype "bidirectional"))
      (node (ref "USB-NATIVE") (pin "SHLD1") (pinfunction "SHLD_SHLD1") (pintype "bidirectional"))
      (node (ref "USB-NATIVE") (pin "SHLD2") (pinfunction "SHLD_SHLD2") (pintype "bidirectional"))
      (node (ref "USB-NATIVE") (pin "SHLD3") (pinfunction "SHLD_SHLD3") (pintype "bidirectional"))
      (node (ref "USB-NATIVE") (pin "SHLD4") (pinfunction "SHLD_SHLD4") (pintype "bidirectional"))
      (node (ref "USB-NATIVE") (pin "SHLD5") (pinfunction "SHLD_SHLD5") (pintype "bidirectional"))
      (node (ref "USB-NATIVE") (pin "SHLD6") (pinfunction "SHLD_SHLD6") (pintype "bidirectional"))
      (node (ref "USB-NATIVE") (pin "SHLD7") (pinfunction "SHLD_SHLD7") (pintype "bidirectional"))
      (node (ref "USB-NATIVE") (pin "SHLD8") (pinfunction "SHLD_SHLD8") (pintype "bidirectional"))
      (node (ref "USB-TTL") (pin "GND") (pinfunction "GND_GND") (pintype "bidirectional"))
      (node (ref "USB-TTL") (pin "GND2") (pinfunction "GND_GND2") (pintype "bidirectional"))
      (node (ref "USB-TTL") (pin "SHLD1") (pinfunction "SHLD_SHLD1") (pintype "bidirectional"))
      (node (ref "USB-TTL") (pin "SHLD2") (pinfunction "SHLD_SHLD2") (pintype "bidirectional"))
      (node (ref "USB-TTL") (pin "SHLD3") (pinfunction "SHLD_SHLD3") (pintype "bidirectional"))
      (node (ref "USB-TTL") (pin "SHLD4") (pinfunction "SHLD_SHLD4") (pintype "bidirectional"))
      (node (ref "USB-TTL") (pin "SHLD5") (pinfunction "SHLD_SHLD5") (pintype "bidirectional"))
      (node (ref "USB-TTL") (pin "SHLD6") (pinfunction "SHLD_SHLD6") (pintype "bidirectional"))
      (node (ref "USB-TTL") (pin "SHLD7") (pinfunction "SHLD_SHLD7") (pintype "bidirectional"))
      (node (ref "USB-TTL") (pin "SHLD8") (pinfunction "SHLD_SHLD8") (pintype "bidirectional"))
    )
    (net (code "49") (name "Net-(D1-PadA)") (class "Default")
      (node (ref "D1") (pin "A") (pinfunction "A_A") (pintype "passive"))
      (node (ref "R15") (pin "2") (pinfunction "2_2") (pintype "passive"))
    )
    (net (code "50") (name "Net-(D4-PadA)") (class "Default")
      (node (ref "D4") (pin "A") (pinfunction "A_A") (pintype "passive"))
      (node (ref "R21") (pin "2") (pinfunction "2_2") (pintype "passive"))
    )
    (net (code "51") (name "Net-(D5-PadA)") (class "Default")
      (node (ref "D5") (pin "A") (pinfunction "A_A") (pintype "passive"))
      (node (ref "R22") (pin "2") (pinfunction "2_2") (pintype "passive"))
    )
    (net (code "52") (name "Net-(D8-PadC)") (class "Default")
      (node (ref "D8") (pin "C") (pinfunction "C_C") (pintype "passive"))
      (node (ref "R28") (pin "1") (pinfunction "1_1") (pintype "passive"))
    )
    (net (code "53") (name "Net-(D9-PadC)") (class "Default")
      (node (ref "D9") (pin "C") (pinfunction "C_C") (pintype "passive"))
      (node (ref "R29") (pin "1") (pinfunction "1_1") (pintype "passive"))
    )
    (net (code "54") (name "Net-(J4-P$2)") (class "Default")
      (node (ref "J4") (pin "2") (pinfunction "P$2_2") (pintype "bidirectional"))
      (node (ref "U1") (pin "4") (pinfunction "SWCLK_4") (pintype "bidirectional"))
    )
    (net (code "55") (name "Net-(J4-P$3)") (class "Default")
      (node (ref "J4") (pin "3") (pinfunction "P$3_3") (pintype "bidirectional"))
      (node (ref "U1") (pin "5") (pinfunction "SWDIO_5") (pintype "bidirectional"))
    )
    (net (code "56") (name "Net-(OLED1-C1N)") (class "Default")
      (node (ref "C27") (pin "2") (pinfunction "2_2") (pintype "passive"))
      (node (ref "OLED1") (pin "5") (pinfunction "C1N_5") (pintype "bidirectional"))
    )
    (net (code "57") (name "Net-(OLED1-C1P)") (class "Default")
      (node (ref "C27") (pin "1") (pinfunction "1_1") (pintype "passive"))
      (node (ref "OLED1") (pin "4") (pinfunction "C1P_4") (pintype "bidirectional"))
    )
    (net (code "58") (name "Net-(OLED1-C2N)") (class "Default")
      (node (ref "C26") (pin "2") (pinfunction "2_2") (pintype "passive"))
      (node (ref "OLED1") (pin "3") (pinfunction "C2N_3") (pintype "bidirectional"))
    )
    (net (code "59") (name "Net-(OLED1-C2P)") (class "Default")
      (node (ref "C26") (pin "1") (pinfunction "1_1") (pintype "passive"))
      (node (ref "OLED1") (pin "2") (pinfunction "C2P_2") (pintype "bidirectional"))
    )
    (net (code "60") (name "Net-(OLED1-D{slash}C#)") (class "Default")
      (node (ref "OLED1") (pin "15") (pinfunction "D/C#_15") (pintype "bidirectional"))
      (node (ref "R25") (pin "1") (pinfunction "1_1") (pintype "passive"))
      (node (ref "R5") (pin "1") (pinfunction "1_1") (pintype "passive"))
    )
    (net (code "61") (name "Net-(OLED1-IREF)") (class "Default")
      (node (ref "OLED1") (pin "26") (pinfunction "IREF_26") (pintype "bidirectional"))
      (node (ref "R26") (pin "1") (pinfunction "1_1") (pintype "passive"))
    )
    (net (code "62") (name "Net-(OLED1-RES#)") (class "Default")
      (node (ref "C17") (pin "2") (pinfunction "2_2") (pintype "passive"))
      (node (ref "D7") (pin "+") (pinfunction "+_+") (pintype "passive"))
      (node (ref "OLED1") (pin "14") (pinfunction "RES#_14") (pintype "bidirectional"))
      (node (ref "R1") (pin "1") (pinfunction "1_1") (pintype "passive"))
    )
    (net (code "63") (name "Net-(OLED1-VCC)") (class "Default")
      (node (ref "C29") (pin "2") (pinfunction "2_2") (pintype "passive"))
      (node (ref "OLED1") (pin "28") (pinfunction "VCC_28") (pintype "bidirectional"))
    )
    (net (code "64") (name "Net-(OLED1-VCOMH)") (class "Default")
      (node (ref "C28") (pin "2") (pinfunction "2_2") (pintype "passive"))
      (node (ref "OLED1") (pin "27") (pinfunction "VCOMH_27") (pintype "bidirectional"))
    )
    (net (code "65") (name "Net-(PWR-PadC)") (class "Default")
      (node (ref "PWR") (pin "C") (pinfunction "C_C") (pintype "passive"))
      (node (ref "R3") (pin "2") (pinfunction "2_2") (pintype "passive"))
    )
    (net (code "66") (name "Net-(Q3-B)") (class "Default")
      (node (ref "Q3") (pin "1") (pinfunction "B_1") (pintype "passive"))
      (node (ref "R11") (pin "1") (pinfunction "1_1") (pintype "passive"))
    )
    (net (code "67") (name "Net-(Q4-B)") (class "Default")
      (node (ref "Q4") (pin "1") (pinfunction "B_1") (pintype "passive"))
      (node (ref "R12") (pin "1") (pinfunction "1_1") (pintype "passive"))
    )
    (net (code "68") (name "Net-(U2-IO19)") (class "Default")
      (node (ref "R64") (pin "2") (pinfunction "2_2") (pintype "passive"))
      (node (ref "U2") (pin "13") (pinfunction "IO19_13") (pintype "bidirectional"))
    )
    (net (code "69") (name "Net-(U2-IO20)") (class "Default")
      (node (ref "R65") (pin "2") (pinfunction "2_2") (pintype "passive"))
      (node (ref "U2") (pin "14") (pinfunction "IO20_14") (pintype "bidirectional"))
    )
    (net (code "70") (name "Net-(U5-BYP)") (class "Default")
      (node (ref "C30") (pin "1") (pinfunction "1_1") (pintype "passive"))
      (node (ref "U5") (pin "4") (pinfunction "BYP_4") (pintype "bidirectional"))
    )
    (net (code "71") (name "Net-(U6-CHRG)") (class "Default")
      (node (ref "R28") (pin "2") (pinfunction "2_2") (pintype "passive"))
      (node (ref "U6") (pin "7") (pinfunction "CHRG_7") (pintype "bidirectional"))
    )
    (net (code "72") (name "Net-(U6-DONE)") (class "Default")
      (node (ref "R29") (pin "2") (pinfunction "2_2") (pintype "passive"))
      (node (ref "U6") (pin "6") (pinfunction "DONE_6") (pintype "bidirectional"))
    )
    (net (code "73") (name "Net-(U6-ISET)") (class "Default")
      (node (ref "R27") (pin "1") (pinfunction "1_1") (pintype "passive"))
      (node (ref "U6") (pin "2") (pinfunction "ISET_2") (pintype "bidirectional"))
    )
    (net (code "74") (name "Net-(U8-RXD)") (class "Default")
      (node (ref "R80") (pin "2") (pinfunction "2_2") (pintype "passive"))
      (node (ref "U8") (pin "9") (pinfunction "RXD_9") (pintype "bidirectional"))
    )
    (net (code "75") (name "Net-(U8-TXD)") (class "Default")
      (node (ref "R79") (pin "2") (pinfunction "2_2") (pintype "passive"))
      (node (ref "U8") (pin "8") (pinfunction "TXD_8") (pintype "bidirectional"))
    )
    (net (code "76") (name "Net-(USB-NATIVE-CC1)") (class "Default")
      (node (ref "R46") (pin "2") (pinfunction "2_2") (pintype "passive"))
      (node (ref "USB-NATIVE") (pin "A5") (pinfunction "CC1_A5") (pintype "bidirectional"))
    )
    (net (code "77") (name "Net-(USB-NATIVE-CC2)") (class "Default")
      (node (ref "R72") (pin "2") (pinfunction "2_2") (pintype "passive"))
      (node (ref "USB-NATIVE") (pin "B5") (pinfunction "CC2_B5") (pintype "bidirectional"))
    )
    (net (code "78") (name "Net-(USB-TTL-CC1)") (class "Default")
      (node (ref "R31") (pin "2") (pinfunction "2_2") (pintype "passive"))
      (node (ref "USB-TTL") (pin "A5") (pinfunction "CC1_A5") (pintype "bidirectional"))
    )
    (net (code "79") (name "Net-(USB-TTL-CC2)") (class "Default")
      (node (ref "R30") (pin "2") (pinfunction "2_2") (pintype "passive"))
      (node (ref "USB-TTL") (pin "B5") (pinfunction "CC2_B5") (pintype "bidirectional"))
    )
    (net (code "80") (name "VBUS") (class "Default")
      (node (ref "C1") (pin "1") (pinfunction "1_1") (pintype "passive"))
      (node (ref "C18") (pin "1") (pinfunction "1_1") (pintype "passive"))
      (node (ref "C19") (pin "1") (pinfunction "1_1") (pintype "passive"))
      (node (ref "C2") (pin "1") (pinfunction "1_1") (pintype "passive"))
      (node (ref "C41") (pin "2") (pinfunction "2_2") (pintype "passive"))
      (node (ref "C44") (pin "2") (pinfunction "2_2") (pintype "passive"))
      (node (ref "C45") (pin "2") (pinfunction "2_2") (pintype "passive"))
      (node (ref "D3") (pin "C") (pinfunction "C_C") (pintype "passive"))
      (node (ref "D6") (pin "A") (pinfunction "A_A") (pintype "passive"))
      (node (ref "D8") (pin "A") (pinfunction "A_A") (pintype "passive"))
      (node (ref "D9") (pin "A") (pinfunction "A_A") (pintype "passive"))
      (node (ref "Q1") (pin "1") (pinfunction "G_1") (pintype "passive"))
      (node (ref "R24") (pin "1") (pinfunction "1_1") (pintype "passive"))
      (node (ref "U6") (pin "4") (pinfunction "VIN_4") (pintype "bidirectional"))
      (node (ref "U6") (pin "8") (pinfunction "CE_8") (pintype "bidirectional"))
      (node (ref "USB-TTL") (pin "VBUS1") (pinfunction "VBUS_VBUS1") (pintype "bidirectional"))
      (node (ref "USB-TTL") (pin "VBUS2") (pinfunction "VBUS_VBUS2") (pintype "bidirectional"))
    )
    (net (code "81") (name "unconnected-(OLED1-NC-Pad7)") (class "Default")
      (node (ref "OLED1") (pin "7") (pinfunction "NC_7") (pintype "bidirectional"))
    )
    (net (code "82") (name "unconnected-(U1-NC-Pad6)") (class "Default")
      (node (ref "U1") (pin "6") (pinfunction "NC_6") (pintype "bidirectional"))
    )
    (net (code "83") (name "unconnected-(U1-NC1-Pad12)") (class "Default")
      (node (ref "U1") (pin "12") (pinfunction "NC1_12") (pintype "bidirectional"))
    )
    (net (code "84") (name "unconnected-(U1-NC2-Pad13)") (class "Default")
      (node (ref "U1") (pin "13") (pinfunction "NC2_13") (pintype "bidirectional"))
    )
    (net (code "85") (name "unconnected-(U1-NC3-Pad14)") (class "Default")
      (node (ref "U1") (pin "14") (pinfunction "NC3_14") (pintype "bidirectional"))
    )
    (net (code "86") (name "unconnected-(U1-NC4-Pad15)") (class "Default")
      (node (ref "U1") (pin "15") (pinfunction "NC4_15") (pintype "bidirectional"))
    )
    (net (code "87") (name "unconnected-(U1-NC5-Pad16)") (class "Default")
      (node (ref "U1") (pin "16") (pinfunction "NC5_16") (pintype "bidirectional"))
    )
    (net (code "88") (name "unconnected-(U1-NC6-Pad21)") (class "Default")
      (node (ref "U1") (pin "21") (pinfunction "NC6_21") (pintype "bidirectional"))
    )
    (net (code "89") (name "unconnected-(U1-NC7-Pad23)") (class "Default")
      (node (ref "U1") (pin "23") (pinfunction "NC7_23") (pintype "bidirectional"))
    )
    (net (code "90") (name "unconnected-(U1-NC8-Pad25)") (class "Default")
      (node (ref "U1") (pin "25") (pinfunction "NC8_25") (pintype "bidirectional"))
    )
    (net (code "91") (name "unconnected-(U1-NC9-Pad26)") (class "Default")
      (node (ref "U1") (pin "26") (pinfunction "NC9_26") (pintype "bidirectional"))
    )
    (net (code "92") (name "unconnected-(U1-NC10-Pad27)") (class "Default")
      (node (ref "U1") (pin "27") (pinfunction "NC10_27") (pintype "bidirectional"))
    )
    (net (code "93") (name "unconnected-(U1-NC11-Pad28)") (class "Default")
      (node (ref "U1") (pin "28") (pinfunction "NC11_28") (pintype "bidirectional"))
    )
    (net (code "94") (name "unconnected-(U1-NC12-Pad29)") (class "Default")
      (node (ref "U1") (pin "29") (pinfunction "NC12_29") (pintype "bidirectional"))
    )
    (net (code "95") (name "unconnected-(U1-NC13-Pad30)") (class "Default")
      (node (ref "U1") (pin "30") (pinfunction "NC13_30") (pintype "bidirectional"))
    )
    (net (code "96") (name "unconnected-(U1-NC14-Pad31)") (class "Default")
      (node (ref "U1") (pin "31") (pinfunction "NC14_31") (pintype "bidirectional"))
    )
    (net (code "97") (name "unconnected-(U1-NC15-Pad32)") (class "Default")
      (node (ref "U1") (pin "32") (pinfunction "NC15_32") (pintype "bidirectional"))
    )
    (net (code "98") (name "unconnected-(U1-TWR-Pad18)") (class "Default")
      (node (ref "U1") (pin "18") (pinfunction "TWR_18") (pintype "bidirectional"))
    )
    (net (code "99") (name "unconnected-(U2-IO35-Pad28)") (class "Default")
      (node (ref "U2") (pin "28") (pinfunction "IO35_28") (pintype "bidirectional"))
    )
    (net (code "100") (name "unconnected-(U2-IO36-Pad29)") (class "Default")
      (node (ref "U2") (pin "29") (pinfunction "IO36_29") (pintype "bidirectional"))
    )
    (net (code "101") (name "unconnected-(U2-IO37-Pad30)") (class "Default")
      (node (ref "U2") (pin "30") (pinfunction "IO37_30") (pintype "bidirectional"))
    )
    (net (code "102") (name "unconnected-(U8-CTS#-Pad5)") (class "Default")
      (node (ref "U8") (pin "5") (pinfunction "CTS#_5") (pintype "bidirectional"))
    )
  )
)
